# projekt_g_wny_1.net
KiCad netlist of a schematic drawn in EAGLE
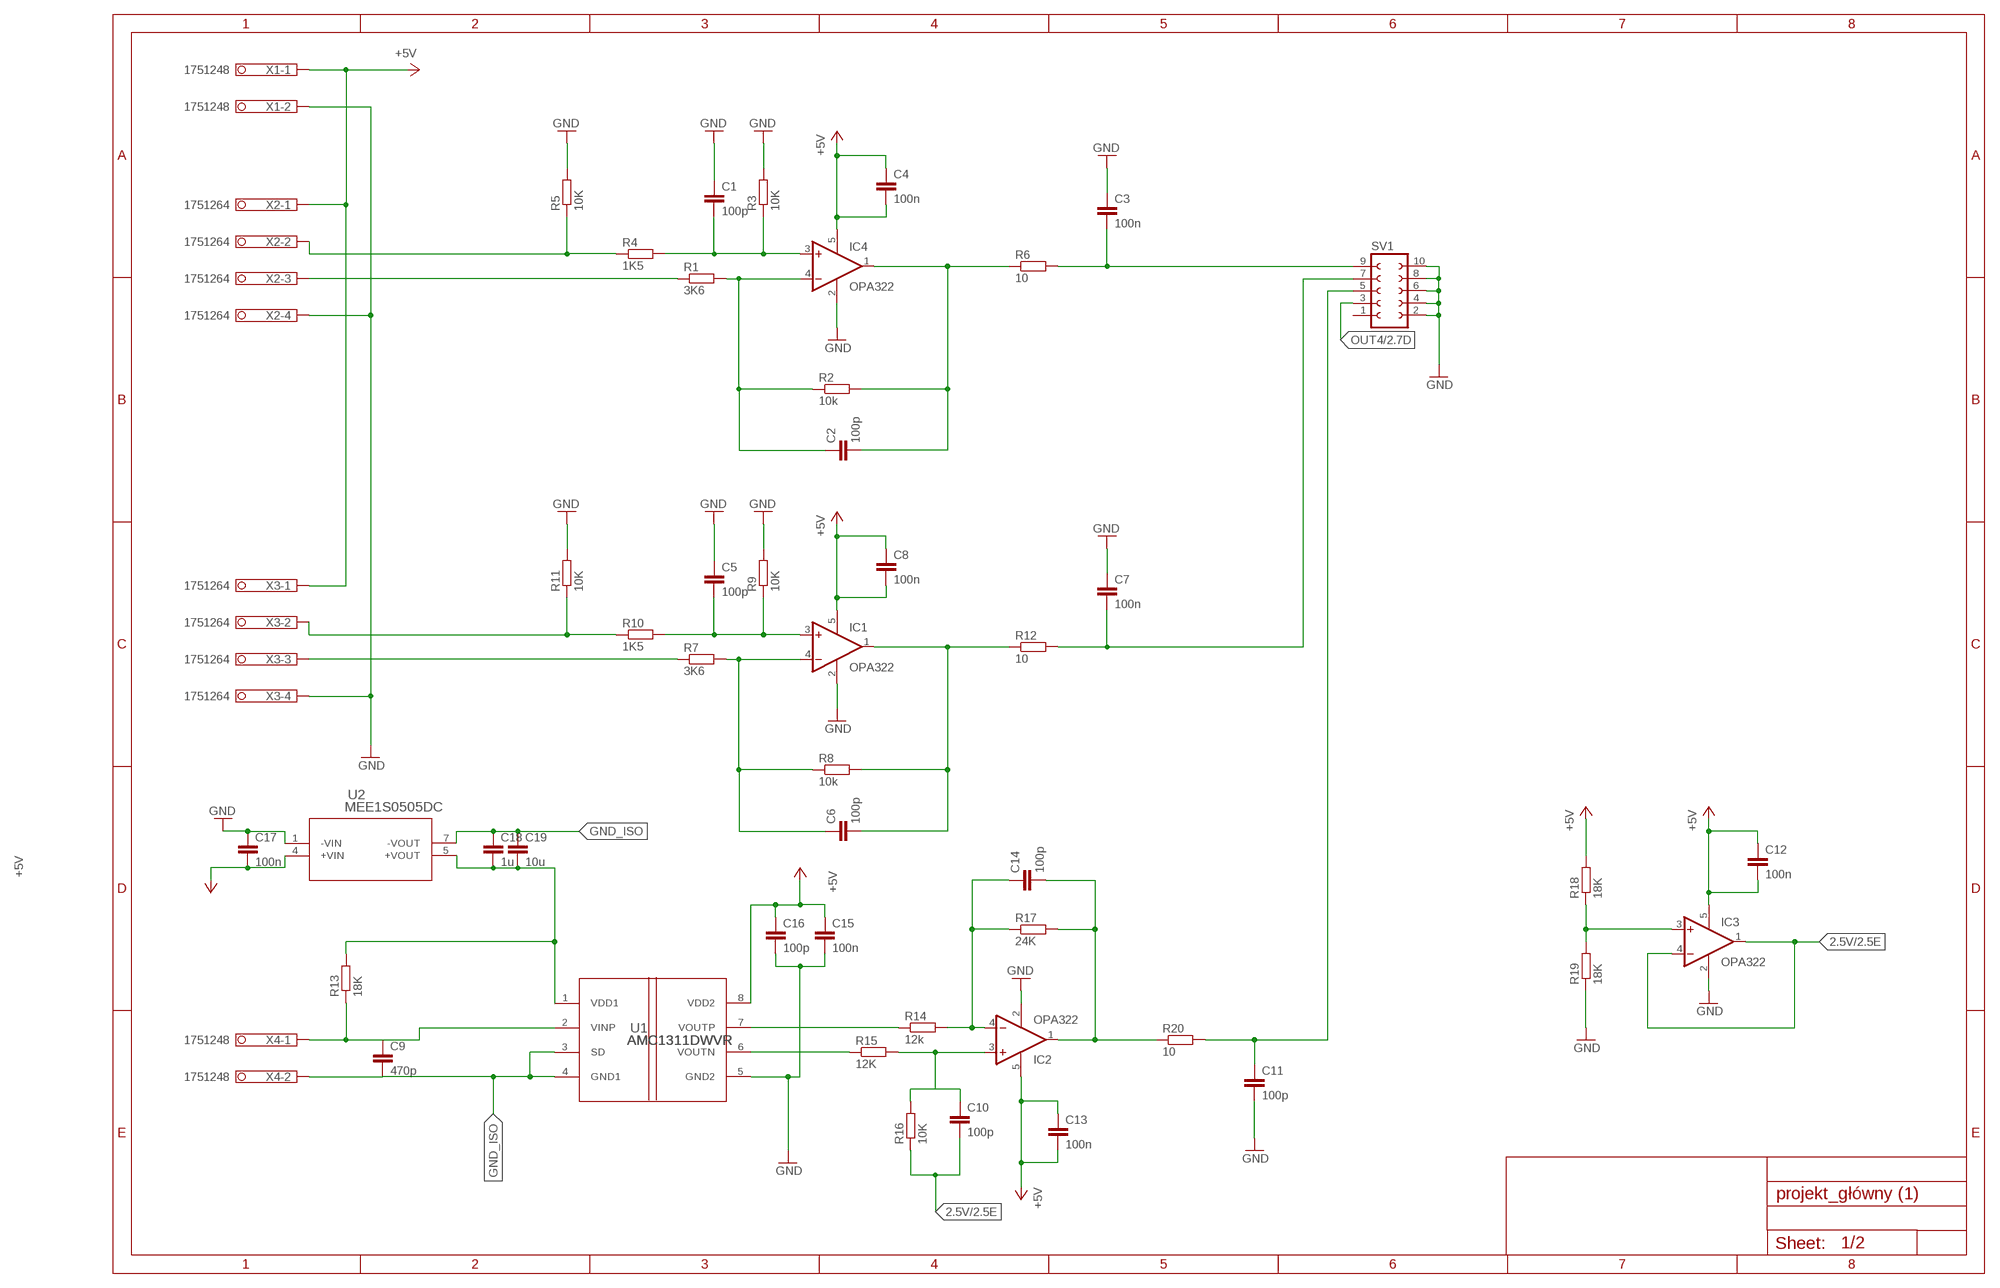
[diagram p0: schematic, sheet 1]
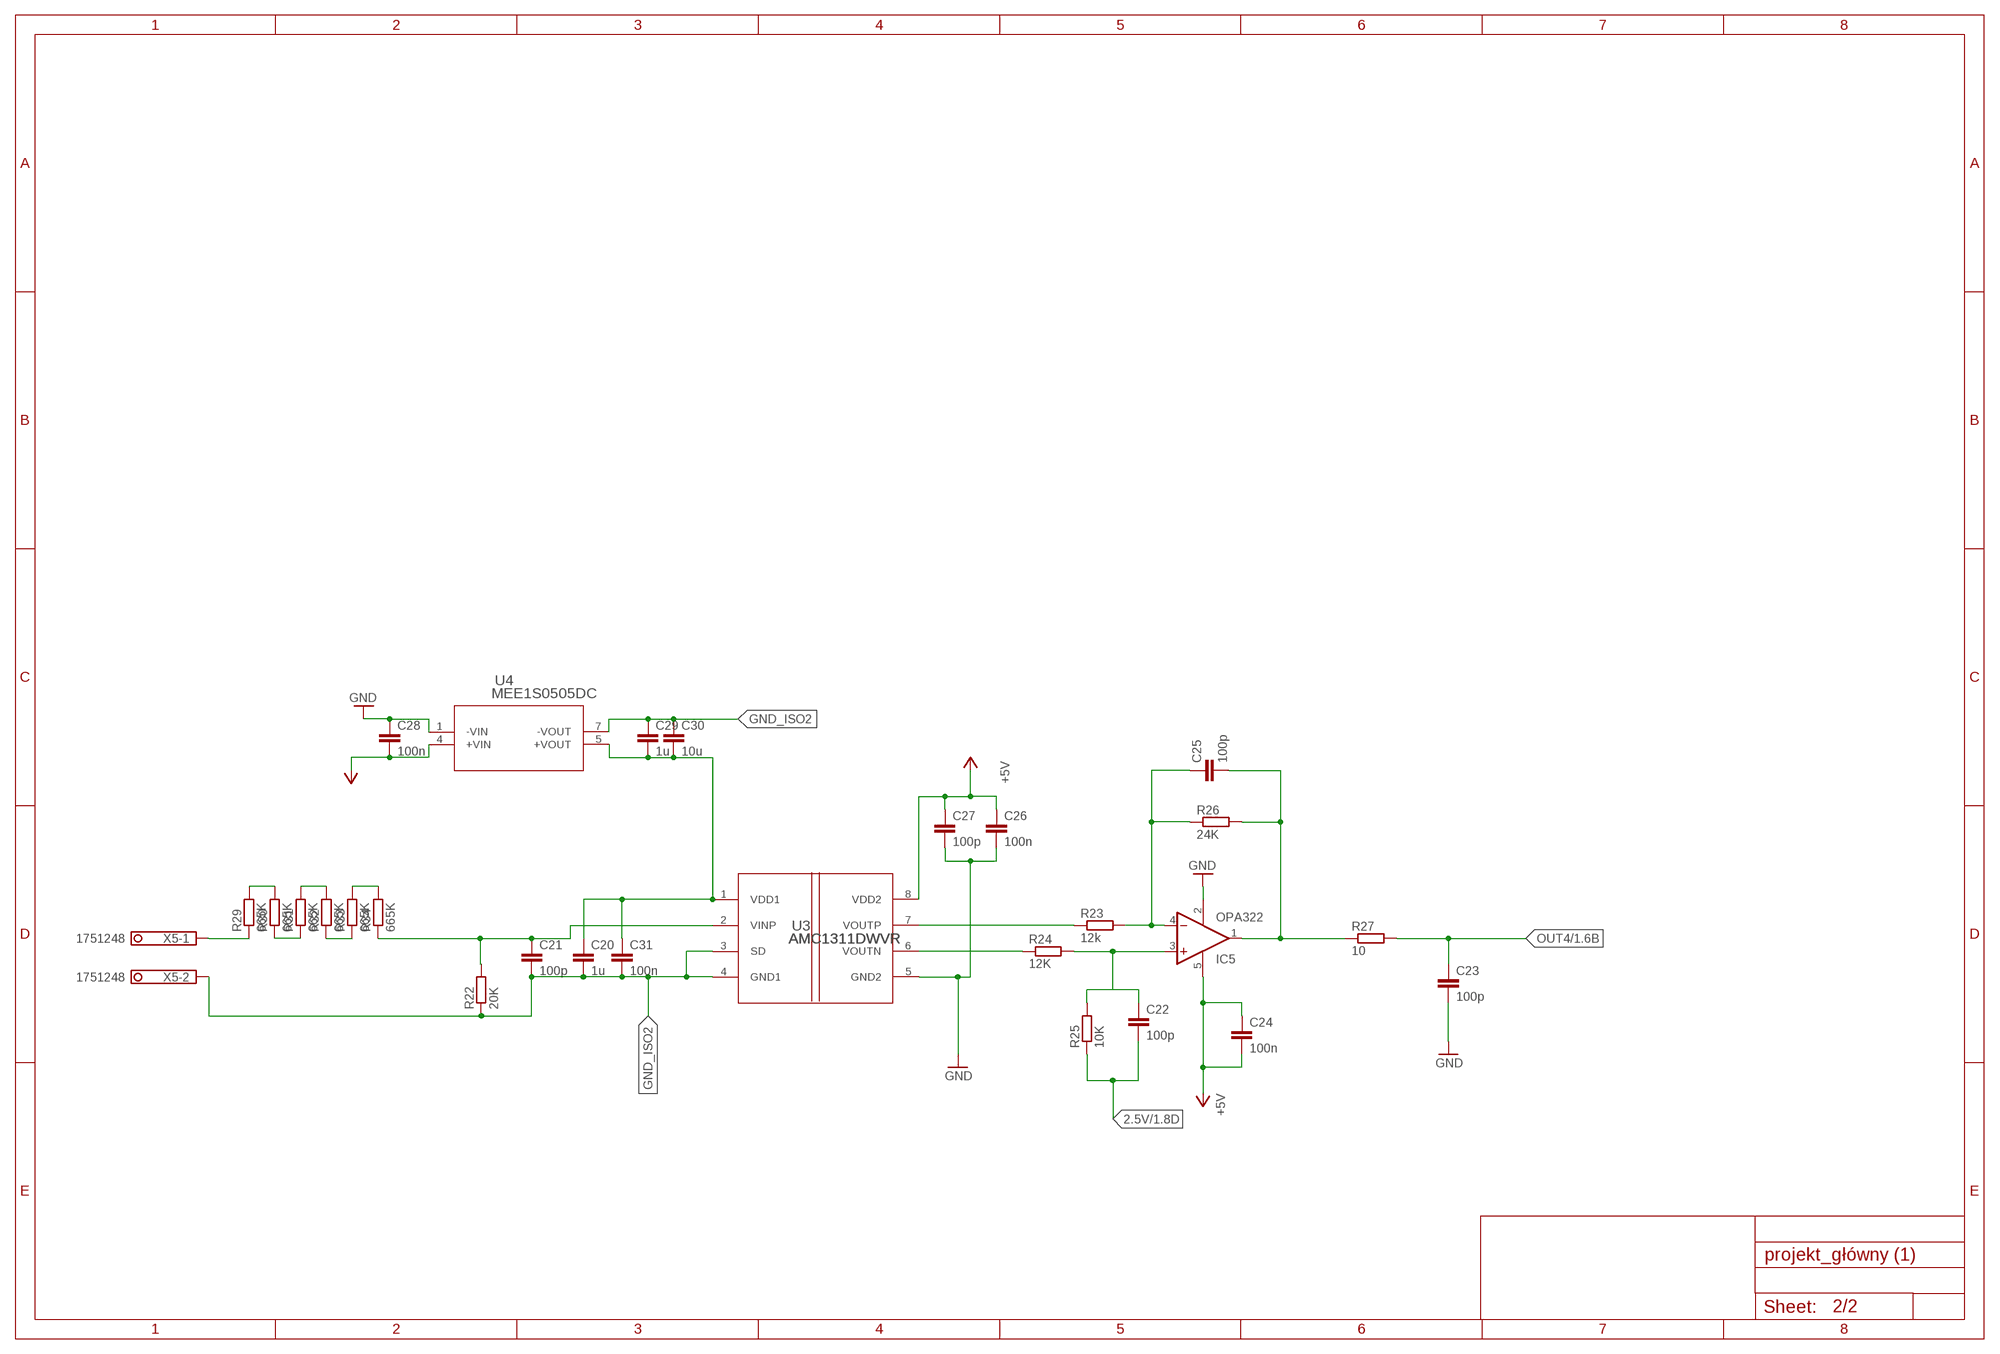
[diagram p1: schematic, sheet 2]

(export (version "E")
  (design (tool "Eeschema 10.0.6"))
  (components
    (comp (ref "C20")
      (value "1u")
      (footprint "eagle-import:C0603")
      (libsource (lib "eagle-import") (part "C-EUC0603"))
    )
    (comp (ref "C21")
      (value "100p")
      (footprint "eagle-import:C0603")
      (libsource (lib "eagle-import") (part "C-EUC0603"))
    )
    (comp (ref "C22")
      (value "100p")
      (footprint "eagle-import:C0603")
      (libsource (lib "eagle-import") (part "C-EUC0603"))
    )
    (comp (ref "C23")
      (value "100p")
      (footprint "eagle-import:C0603")
      (libsource (lib "eagle-import") (part "C-EUC0603"))
    )
    (comp (ref "C24")
      (value "100n")
      (footprint "eagle-import:C0603")
      (libsource (lib "eagle-import") (part "C-EUC0603"))
    )
    (comp (ref "C25")
      (value "100p")
      (footprint "eagle-import:C0603")
      (libsource (lib "eagle-import") (part "C-EUC0603"))
    )
    (comp (ref "C26")
      (value "100n")
      (footprint "eagle-import:C0603")
      (libsource (lib "eagle-import") (part "C-EUC0603"))
    )
    (comp (ref "C27")
      (value "100p")
      (footprint "eagle-import:C0603")
      (libsource (lib "eagle-import") (part "C-EUC0603"))
    )
    (comp (ref "C28")
      (value "100n")
      (footprint "eagle-import:C0603")
      (libsource (lib "eagle-import") (part "C-EUC0603"))
    )
    (comp (ref "C29")
      (value "1u")
      (footprint "eagle-import:C0603")
      (libsource (lib "eagle-import") (part "C-EUC0603"))
    )
    (comp (ref "C30")
      (value "10u")
      (footprint "eagle-import:C0603")
      (libsource (lib "eagle-import") (part "C-EUC0603"))
    )
    (comp (ref "C31")
      (value "100n")
      (footprint "eagle-import:C0603")
      (libsource (lib "eagle-import") (part "C-EUC0603"))
    )
    (comp (ref "IC5")
      (value "OPA322")
      (footprint "eagle-import:SOT23-5")
      (libsource (lib "eagle-import") (part "OPA333DBV"))
    )
    (comp (ref "R22")
      (value "20K")
      (footprint "eagle-import:R0805")
      (libsource (lib "eagle-import") (part "R-EU_R0805"))
    )
    (comp (ref "R23")
      (value "12k")
      (footprint "eagle-import:R0805")
      (libsource (lib "eagle-import") (part "R-EU_R0805"))
    )
    (comp (ref "R24")
      (value "12K")
      (footprint "eagle-import:R0805")
      (libsource (lib "eagle-import") (part "R-EU_R0805"))
    )
    (comp (ref "R25")
      (value "10K")
      (footprint "eagle-import:R0805")
      (libsource (lib "eagle-import") (part "R-EU_R0805"))
    )
    (comp (ref "R26")
      (value "24K")
      (footprint "eagle-import:R0805")
      (libsource (lib "eagle-import") (part "R-EU_R0805"))
    )
    (comp (ref "R27")
      (value "10")
      (footprint "eagle-import:R0805")
      (libsource (lib "eagle-import") (part "R-EU_R0805"))
    )
    (comp (ref "R29")
      (value "665K")
      (footprint "eagle-import:R0805")
      (libsource (lib "eagle-import") (part "R-EU_R0805"))
    )
    (comp (ref "R30")
      (value "665K")
      (footprint "eagle-import:R0805")
      (libsource (lib "eagle-import") (part "R-EU_R0805"))
    )
    (comp (ref "R31")
      (value "665K")
      (footprint "eagle-import:R0805")
      (libsource (lib "eagle-import") (part "R-EU_R0805"))
    )
    (comp (ref "R32")
      (value "665K")
      (footprint "eagle-import:R0805")
      (libsource (lib "eagle-import") (part "R-EU_R0805"))
    )
    (comp (ref "R33")
      (value "665K")
      (footprint "eagle-import:R0805")
      (libsource (lib "eagle-import") (part "R-EU_R0805"))
    )
    (comp (ref "R34")
      (value "665K")
      (footprint "eagle-import:R0805")
      (libsource (lib "eagle-import") (part "R-EU_R0805"))
    )
    (comp (ref "U3")
      (value "AMC1311DWVR")
      (footprint "eagle-import:DWV0008A")
      (fields (field (name "COPYRIGHT") "Copyright (C) 2023 Ultra Librarian. All rights reserved."))
      (libsource (lib "eagle-import") (part "AMC1311DWVR"))
    )
    (comp (ref "U4")
      (value "MEE1S0505DC")
      (footprint "eagle-import:MEE1S0305DC_MUR")
      (fields
        (field (name "MANUFACTURER_PART_NUMBER") "MEE1S0305DC")
        (field (name "COPYRIGHT") "Copyright (C) 2023 Ultra Librarian. All rights reserved.")
      )
      (libsource (lib "eagle-import") (part "MEE1S0305DC"))
    )
    (comp (ref "X5")
      (value "1751248")
      (footprint "eagle-import:1751248")
      (libsource (lib "eagle-import") (part "1751248"))
    )
    (comp (ref "C1")
      (value "100p")
      (footprint "eagle-import:C0603")
      (libsource (lib "eagle-import") (part "C-EUC0603"))
    )
    (comp (ref "C2")
      (value "100p")
      (footprint "eagle-import:C0603")
      (libsource (lib "eagle-import") (part "C-EUC0603"))
    )
    (comp (ref "C3")
      (value "100n")
      (footprint "eagle-import:C0603")
      (libsource (lib "eagle-import") (part "C-EUC0603"))
    )
    (comp (ref "C4")
      (value "100n")
      (footprint "eagle-import:C0603")
      (libsource (lib "eagle-import") (part "C-EUC0603"))
    )
    (comp (ref "C5")
      (value "100p")
      (footprint "eagle-import:C0603")
      (libsource (lib "eagle-import") (part "C-EUC0603"))
    )
    (comp (ref "C6")
      (value "100p")
      (footprint "eagle-import:C0603")
      (libsource (lib "eagle-import") (part "C-EUC0603"))
    )
    (comp (ref "C7")
      (value "100n")
      (footprint "eagle-import:C0603")
      (libsource (lib "eagle-import") (part "C-EUC0603"))
    )
    (comp (ref "C8")
      (value "100n")
      (footprint "eagle-import:C0603")
      (libsource (lib "eagle-import") (part "C-EUC0603"))
    )
    (comp (ref "C9")
      (value "470p")
      (footprint "eagle-import:C0603")
      (libsource (lib "eagle-import") (part "C-EUC0603"))
    )
    (comp (ref "C10")
      (value "100p")
      (footprint "eagle-import:C0603")
      (libsource (lib "eagle-import") (part "C-EUC0603"))
    )
    (comp (ref "C11")
      (value "100p")
      (footprint "eagle-import:C0603")
      (libsource (lib "eagle-import") (part "C-EUC0603"))
    )
    (comp (ref "C12")
      (value "100n")
      (footprint "eagle-import:C0603")
      (libsource (lib "eagle-import") (part "C-EUC0603"))
    )
    (comp (ref "C13")
      (value "100n")
      (footprint "eagle-import:C0603")
      (libsource (lib "eagle-import") (part "C-EUC0603"))
    )
    (comp (ref "C14")
      (value "100p")
      (footprint "eagle-import:C0603")
      (libsource (lib "eagle-import") (part "C-EUC0603"))
    )
    (comp (ref "C15")
      (value "100n")
      (footprint "eagle-import:C0603")
      (libsource (lib "eagle-import") (part "C-EUC0603"))
    )
    (comp (ref "C16")
      (value "100p")
      (footprint "eagle-import:C0603")
      (libsource (lib "eagle-import") (part "C-EUC0603"))
    )
    (comp (ref "C17")
      (value "100n")
      (footprint "eagle-import:C0603")
      (libsource (lib "eagle-import") (part "C-EUC0603"))
    )
    (comp (ref "C18")
      (value "1u")
      (footprint "eagle-import:C0603")
      (libsource (lib "eagle-import") (part "C-EUC0603"))
    )
    (comp (ref "C19")
      (value "10u")
      (footprint "eagle-import:C0603")
      (libsource (lib "eagle-import") (part "C-EUC0603"))
    )
    (comp (ref "IC1")
      (value "OPA322")
      (footprint "eagle-import:SOT23-5")
      (libsource (lib "eagle-import") (part "OPA333DBV"))
    )
    (comp (ref "IC2")
      (value "OPA322")
      (footprint "eagle-import:SOT23-5")
      (libsource (lib "eagle-import") (part "OPA333DBV"))
    )
    (comp (ref "IC3")
      (value "OPA322")
      (footprint "eagle-import:SOT23-5")
      (libsource (lib "eagle-import") (part "OPA333DBV"))
    )
    (comp (ref "IC4")
      (value "OPA322")
      (footprint "eagle-import:SOT23-5")
      (libsource (lib "eagle-import") (part "OPA333DBV"))
    )
    (comp (ref "R1")
      (value "3K6")
      (footprint "eagle-import:R0805")
      (libsource (lib "eagle-import") (part "R-EU_R0805"))
    )
    (comp (ref "R2")
      (value "10k")
      (footprint "eagle-import:R0805")
      (libsource (lib "eagle-import") (part "R-EU_R0805"))
    )
    (comp (ref "R3")
      (value "10K")
      (footprint "eagle-import:R0805")
      (libsource (lib "eagle-import") (part "R-EU_R0805"))
    )
    (comp (ref "R4")
      (value "1K5")
      (footprint "eagle-import:R0805")
      (libsource (lib "eagle-import") (part "R-EU_R0805"))
    )
    (comp (ref "R5")
      (value "10K")
      (footprint "eagle-import:R0805")
      (libsource (lib "eagle-import") (part "R-EU_R0805"))
    )
    (comp (ref "R6")
      (value "10")
      (footprint "eagle-import:R0805")
      (libsource (lib "eagle-import") (part "R-EU_R0805"))
    )
    (comp (ref "R7")
      (value "3K6")
      (footprint "eagle-import:R0805")
      (libsource (lib "eagle-import") (part "R-EU_R0805"))
    )
    (comp (ref "R8")
      (value "10k")
      (footprint "eagle-import:R0805")
      (libsource (lib "eagle-import") (part "R-EU_R0805"))
    )
    (comp (ref "R9")
      (value "10K")
      (footprint "eagle-import:R0805")
      (libsource (lib "eagle-import") (part "R-EU_R0805"))
    )
    (comp (ref "R10")
      (value "1K5")
      (footprint "eagle-import:R0805")
      (libsource (lib "eagle-import") (part "R-EU_R0805"))
    )
    (comp (ref "R11")
      (value "10K")
      (footprint "eagle-import:R0805")
      (libsource (lib "eagle-import") (part "R-EU_R0805"))
    )
    (comp (ref "R12")
      (value "10")
      (footprint "eagle-import:R0805")
      (libsource (lib "eagle-import") (part "R-EU_R0805"))
    )
    (comp (ref "R13")
      (value "18K")
      (footprint "eagle-import:R0805")
      (libsource (lib "eagle-import") (part "R-EU_R0805"))
    )
    (comp (ref "R14")
      (value "12k")
      (footprint "eagle-import:R0805")
      (libsource (lib "eagle-import") (part "R-EU_R0805"))
    )
    (comp (ref "R15")
      (value "12K")
      (footprint "eagle-import:R0805")
      (libsource (lib "eagle-import") (part "R-EU_R0805"))
    )
    (comp (ref "R16")
      (value "10K")
      (footprint "eagle-import:R0805")
      (libsource (lib "eagle-import") (part "R-EU_R0805"))
    )
    (comp (ref "R17")
      (value "24K")
      (footprint "eagle-import:R0805")
      (libsource (lib "eagle-import") (part "R-EU_R0805"))
    )
    (comp (ref "R18")
      (value "18K")
      (footprint "eagle-import:R0805")
      (libsource (lib "eagle-import") (part "R-EU_R0805"))
    )
    (comp (ref "R19")
      (value "18K")
      (footprint "eagle-import:R0805")
      (libsource (lib "eagle-import") (part "R-EU_R0805"))
    )
    (comp (ref "R20")
      (value "10")
      (footprint "eagle-import:R0805")
      (libsource (lib "eagle-import") (part "R-EU_R0805"))
    )
    (comp (ref "SV1")
      (value "FE05-2")
      (footprint "eagle-import:FE05-2")
      (libsource (lib "eagle-import") (part "FE05-2"))
    )
    (comp (ref "U1")
      (value "AMC1311DWVR")
      (footprint "eagle-import:DWV0008A")
      (fields (field (name "COPYRIGHT") "Copyright (C) 2023 Ultra Librarian. All rights reserved."))
      (libsource (lib "eagle-import") (part "AMC1311DWVR"))
    )
    (comp (ref "U2")
      (value "MEE1S0505DC")
      (footprint "eagle-import:MEE1S0305DC_MUR")
      (fields
        (field (name "MANUFACTURER_PART_NUMBER") "MEE1S0305DC")
        (field (name "COPYRIGHT") "Copyright (C) 2023 Ultra Librarian. All rights reserved.")
      )
      (libsource (lib "eagle-import") (part "MEE1S0305DC"))
    )
    (comp (ref "X1")
      (value "1751248")
      (footprint "eagle-import:1751248")
      (libsource (lib "eagle-import") (part "1751248"))
    )
    (comp (ref "X2")
      (value "1751264")
      (footprint "eagle-import:1751264")
      (libsource (lib "eagle-import") (part "1751264"))
    )
    (comp (ref "X3")
      (value "1751264")
      (footprint "eagle-import:1751264")
      (libsource (lib "eagle-import") (part "1751264"))
    )
    (comp (ref "X4")
      (value "1751248")
      (footprint "eagle-import:1751248")
      (libsource (lib "eagle-import") (part "1751248"))
    )
  )
  (nets
    (net (code "1") (name "+5V") (class "Default")
      (node (ref "C12") (pin "1") (pinfunction "1_1") (pintype "passive"))
      (node (ref "C12") (pin "2") (pinfunction "2_2") (pintype "passive"))
      (node (ref "C13") (pin "1") (pinfunction "1_1") (pintype "passive"))
      (node (ref "C13") (pin "2") (pinfunction "2_2") (pintype "passive"))
      (node (ref "C15") (pin "1") (pinfunction "1_1") (pintype "passive"))
      (node (ref "C16") (pin "1") (pinfunction "1_1") (pintype "passive"))
      (node (ref "C17") (pin "2") (pinfunction "2_2") (pintype "passive"))
      (node (ref "C24") (pin "1") (pinfunction "1_1") (pintype "passive"))
      (node (ref "C24") (pin "2") (pinfunction "2_2") (pintype "passive"))
      (node (ref "C26") (pin "1") (pinfunction "1_1") (pintype "passive"))
      (node (ref "C27") (pin "1") (pinfunction "1_1") (pintype "passive"))
      (node (ref "C28") (pin "2") (pinfunction "2_2") (pintype "passive"))
      (node (ref "C4") (pin "1") (pinfunction "1_1") (pintype "passive"))
      (node (ref "C4") (pin "2") (pinfunction "2_2") (pintype "passive"))
      (node (ref "C8") (pin "1") (pinfunction "1_1") (pintype "passive"))
      (node (ref "C8") (pin "2") (pinfunction "2_2") (pintype "passive"))
      (node (ref "IC1") (pin "5") (pinfunction "V+_5") (pintype "power_in"))
      (node (ref "IC2") (pin "5") (pinfunction "V+_5") (pintype "power_in"))
      (node (ref "IC3") (pin "5") (pinfunction "V+_5") (pintype "power_in"))
      (node (ref "IC4") (pin "5") (pinfunction "V+_5") (pintype "power_in"))
      (node (ref "IC5") (pin "5") (pinfunction "V+_5") (pintype "power_in"))
      (node (ref "R18") (pin "2") (pinfunction "2_2") (pintype "passive"))
      (node (ref "U1") (pin "8") (pinfunction "VDD2_8") (pintype "power_in"))
      (node (ref "U2") (pin "4") (pinfunction "+VIN_4") (pintype "power_in"))
      (node (ref "U3") (pin "8") (pinfunction "VDD2_8") (pintype "power_in"))
      (node (ref "U4") (pin "4") (pinfunction "+VIN_4") (pintype "power_in"))
      (node (ref "X1") (pin "1") (pinfunction "K_1") (pintype "passive"))
      (node (ref "X2") (pin "1") (pinfunction "K_1") (pintype "passive"))
      (node (ref "X3") (pin "1") (pinfunction "K_1") (pintype "passive"))
    )
    (net (code "2") (name "2.5V") (class "Default")
      (node (ref "C10") (pin "2") (pinfunction "2_2") (pintype "passive"))
      (node (ref "C22") (pin "2") (pinfunction "2_2") (pintype "passive"))
      (node (ref "IC3") (pin "1") (pinfunction "OUT_1") (pintype "output"))
      (node (ref "IC3") (pin "4") (pinfunction "-IN_4") (pintype "input"))
      (node (ref "R16") (pin "1") (pinfunction "1_1") (pintype "passive"))
      (node (ref "R25") (pin "1") (pinfunction "1_1") (pintype "passive"))
    )
    (net (code "3") (name "GND") (class "Default")
      (node (ref "C1") (pin "1") (pinfunction "1_1") (pintype "passive"))
      (node (ref "C11") (pin "2") (pinfunction "2_2") (pintype "passive"))
      (node (ref "C15") (pin "2") (pinfunction "2_2") (pintype "passive"))
      (node (ref "C16") (pin "2") (pinfunction "2_2") (pintype "passive"))
      (node (ref "C17") (pin "1") (pinfunction "1_1") (pintype "passive"))
      (node (ref "C23") (pin "2") (pinfunction "2_2") (pintype "passive"))
      (node (ref "C26") (pin "2") (pinfunction "2_2") (pintype "passive"))
      (node (ref "C27") (pin "2") (pinfunction "2_2") (pintype "passive"))
      (node (ref "C28") (pin "1") (pinfunction "1_1") (pintype "passive"))
      (node (ref "C3") (pin "1") (pinfunction "1_1") (pintype "passive"))
      (node (ref "C5") (pin "1") (pinfunction "1_1") (pintype "passive"))
      (node (ref "C7") (pin "1") (pinfunction "1_1") (pintype "passive"))
      (node (ref "IC1") (pin "2") (pinfunction "V-_2") (pintype "power_in"))
      (node (ref "IC2") (pin "2") (pinfunction "V-_2") (pintype "power_in"))
      (node (ref "IC3") (pin "2") (pinfunction "V-_2") (pintype "power_in"))
      (node (ref "IC4") (pin "2") (pinfunction "V-_2") (pintype "power_in"))
      (node (ref "IC5") (pin "2") (pinfunction "V-_2") (pintype "power_in"))
      (node (ref "R11") (pin "2") (pinfunction "2_2") (pintype "passive"))
      (node (ref "R19") (pin "1") (pinfunction "1_1") (pintype "passive"))
      (node (ref "R3") (pin "2") (pinfunction "2_2") (pintype "passive"))
      (node (ref "R5") (pin "2") (pinfunction "2_2") (pintype "passive"))
      (node (ref "R9") (pin "2") (pinfunction "2_2") (pintype "passive"))
      (node (ref "SV1") (pin "10") (pinfunction "10_10") (pintype "passive"))
      (node (ref "SV1") (pin "2") (pinfunction "2_2") (pintype "passive"))
      (node (ref "SV1") (pin "4") (pinfunction "4_4") (pintype "passive"))
      (node (ref "SV1") (pin "6") (pinfunction "6_6") (pintype "passive"))
      (node (ref "SV1") (pin "8") (pinfunction "8_8") (pintype "passive"))
      (node (ref "U1") (pin "5") (pinfunction "GND2_5") (pintype "power_in"))
      (node (ref "U2") (pin "1") (pinfunction "-VIN_1") (pintype "power_in"))
      (node (ref "U3") (pin "5") (pinfunction "GND2_5") (pintype "power_in"))
      (node (ref "U4") (pin "1") (pinfunction "-VIN_1") (pintype "power_in"))
      (node (ref "X1") (pin "2") (pinfunction "K_2") (pintype "passive"))
      (node (ref "X2") (pin "4") (pinfunction "K_4") (pintype "passive"))
      (node (ref "X3") (pin "4") (pinfunction "K_4") (pintype "passive"))
    )
    (net (code "4") (name "GND_ISO") (class "Default")
      (node (ref "C18") (pin "1") (pinfunction "1_1") (pintype "passive"))
      (node (ref "C19") (pin "1") (pinfunction "1_1") (pintype "passive"))
      (node (ref "C9") (pin "2") (pinfunction "2_2") (pintype "passive"))
      (node (ref "U1") (pin "3") (pinfunction "SD_3") (pintype "input"))
      (node (ref "U1") (pin "4") (pinfunction "GND1_4") (pintype "power_in"))
      (node (ref "U2") (pin "7") (pinfunction "-VOUT_7") (pintype "output"))
      (node (ref "X4") (pin "2") (pinfunction "K_2") (pintype "passive"))
    )
    (net (code "5") (name "GND_ISO2") (class "Default")
      (node (ref "C20") (pin "2") (pinfunction "2_2") (pintype "passive"))
      (node (ref "C21") (pin "2") (pinfunction "2_2") (pintype "passive"))
      (node (ref "C29") (pin "1") (pinfunction "1_1") (pintype "passive"))
      (node (ref "C30") (pin "1") (pinfunction "1_1") (pintype "passive"))
      (node (ref "C31") (pin "2") (pinfunction "2_2") (pintype "passive"))
      (node (ref "R22") (pin "1") (pinfunction "1_1") (pintype "passive"))
      (node (ref "U3") (pin "3") (pinfunction "SD_3") (pintype "input"))
      (node (ref "U3") (pin "4") (pinfunction "GND1_4") (pintype "power_in"))
      (node (ref "U4") (pin "7") (pinfunction "-VOUT_7") (pintype "output"))
      (node (ref "X5") (pin "2") (pinfunction "K_2") (pintype "passive"))
    )
    (net (code "6") (name "Net-(C3-Pad2)") (class "Default")
      (node (ref "C3") (pin "2") (pinfunction "2_2") (pintype "passive"))
      (node (ref "R6") (pin "2") (pinfunction "2_2") (pintype "passive"))
      (node (ref "SV1") (pin "9") (pinfunction "9_9") (pintype "passive"))
    )
    (net (code "7") (name "Net-(C7-Pad2)") (class "Default")
      (node (ref "C7") (pin "2") (pinfunction "2_2") (pintype "passive"))
      (node (ref "R12") (pin "2") (pinfunction "2_2") (pintype "passive"))
      (node (ref "SV1") (pin "7") (pinfunction "7_7") (pintype "passive"))
    )
    (net (code "8") (name "Net-(C11-Pad1)") (class "Default")
      (node (ref "C11") (pin "1") (pinfunction "1_1") (pintype "passive"))
      (node (ref "R20") (pin "2") (pinfunction "2_2") (pintype "passive"))
      (node (ref "SV1") (pin "5") (pinfunction "5_5") (pintype "passive"))
    )
    (net (code "9") (name "Net-(IC1-+IN)") (class "Default")
      (node (ref "C5") (pin "2") (pinfunction "2_2") (pintype "passive"))
      (node (ref "IC1") (pin "3") (pinfunction "+IN_3") (pintype "input"))
      (node (ref "R10") (pin "2") (pinfunction "2_2") (pintype "passive"))
      (node (ref "R9") (pin "1") (pinfunction "1_1") (pintype "passive"))
    )
    (net (code "10") (name "Net-(IC1--IN)") (class "Default")
      (node (ref "C6") (pin "1") (pinfunction "1_1") (pintype "passive"))
      (node (ref "IC1") (pin "4") (pinfunction "-IN_4") (pintype "input"))
      (node (ref "R7") (pin "2") (pinfunction "2_2") (pintype "passive"))
      (node (ref "R8") (pin "1") (pinfunction "1_1") (pintype "passive"))
    )
    (net (code "11") (name "Net-(IC1-OUT)") (class "Default")
      (node (ref "C6") (pin "2") (pinfunction "2_2") (pintype "passive"))
      (node (ref "IC1") (pin "1") (pinfunction "OUT_1") (pintype "output"))
      (node (ref "R12") (pin "1") (pinfunction "1_1") (pintype "passive"))
      (node (ref "R8") (pin "2") (pinfunction "2_2") (pintype "passive"))
    )
    (net (code "12") (name "Net-(IC2-+IN)") (class "Default")
      (node (ref "C10") (pin "1") (pinfunction "1_1") (pintype "passive"))
      (node (ref "IC2") (pin "3") (pinfunction "+IN_3") (pintype "input"))
      (node (ref "R15") (pin "2") (pinfunction "2_2") (pintype "passive"))
      (node (ref "R16") (pin "2") (pinfunction "2_2") (pintype "passive"))
    )
    (net (code "13") (name "Net-(IC2--IN)") (class "Default")
      (node (ref "C14") (pin "1") (pinfunction "1_1") (pintype "passive"))
      (node (ref "IC2") (pin "4") (pinfunction "-IN_4") (pintype "input"))
      (node (ref "R14") (pin "2") (pinfunction "2_2") (pintype "passive"))
      (node (ref "R17") (pin "1") (pinfunction "1_1") (pintype "passive"))
    )
    (net (code "14") (name "Net-(IC2-OUT)") (class "Default")
      (node (ref "C14") (pin "2") (pinfunction "2_2") (pintype "passive"))
      (node (ref "IC2") (pin "1") (pinfunction "OUT_1") (pintype "output"))
      (node (ref "R17") (pin "2") (pinfunction "2_2") (pintype "passive"))
      (node (ref "R20") (pin "1") (pinfunction "1_1") (pintype "passive"))
    )
    (net (code "15") (name "Net-(IC3-+IN)") (class "Default")
      (node (ref "IC3") (pin "3") (pinfunction "+IN_3") (pintype "input"))
      (node (ref "R18") (pin "1") (pinfunction "1_1") (pintype "passive"))
      (node (ref "R19") (pin "2") (pinfunction "2_2") (pintype "passive"))
    )
    (net (code "16") (name "Net-(IC4-+IN)") (class "Default")
      (node (ref "C1") (pin "2") (pinfunction "2_2") (pintype "passive"))
      (node (ref "IC4") (pin "3") (pinfunction "+IN_3") (pintype "input"))
      (node (ref "R3") (pin "1") (pinfunction "1_1") (pintype "passive"))
      (node (ref "R4") (pin "2") (pinfunction "2_2") (pintype "passive"))
    )
    (net (code "17") (name "Net-(IC4--IN)") (class "Default")
      (node (ref "C2") (pin "1") (pinfunction "1_1") (pintype "passive"))
      (node (ref "IC4") (pin "4") (pinfunction "-IN_4") (pintype "input"))
      (node (ref "R1") (pin "2") (pinfunction "2_2") (pintype "passive"))
      (node (ref "R2") (pin "1") (pinfunction "1_1") (pintype "passive"))
    )
    (net (code "18") (name "Net-(IC4-OUT)") (class "Default")
      (node (ref "C2") (pin "2") (pinfunction "2_2") (pintype "passive"))
      (node (ref "IC4") (pin "1") (pinfunction "OUT_1") (pintype "output"))
      (node (ref "R2") (pin "2") (pinfunction "2_2") (pintype "passive"))
      (node (ref "R6") (pin "1") (pinfunction "1_1") (pintype "passive"))
    )
    (net (code "19") (name "Net-(IC5-+IN)") (class "Default")
      (node (ref "C22") (pin "1") (pinfunction "1_1") (pintype "passive"))
      (node (ref "IC5") (pin "3") (pinfunction "+IN_3") (pintype "input"))
      (node (ref "R24") (pin "2") (pinfunction "2_2") (pintype "passive"))
      (node (ref "R25") (pin "2") (pinfunction "2_2") (pintype "passive"))
    )
    (net (code "20") (name "Net-(IC5--IN)") (class "Default")
      (node (ref "C25") (pin "1") (pinfunction "1_1") (pintype "passive"))
      (node (ref "IC5") (pin "4") (pinfunction "-IN_4") (pintype "input"))
      (node (ref "R23") (pin "2") (pinfunction "2_2") (pintype "passive"))
      (node (ref "R26") (pin "1") (pinfunction "1_1") (pintype "passive"))
    )
    (net (code "21") (name "Net-(IC5-OUT)") (class "Default")
      (node (ref "C25") (pin "2") (pinfunction "2_2") (pintype "passive"))
      (node (ref "IC5") (pin "1") (pinfunction "OUT_1") (pintype "output"))
      (node (ref "R26") (pin "2") (pinfunction "2_2") (pintype "passive"))
      (node (ref "R27") (pin "1") (pinfunction "1_1") (pintype "passive"))
    )
    (net (code "22") (name "Net-(R29-Pad2)") (class "Default")
      (node (ref "R29") (pin "2") (pinfunction "2_2") (pintype "passive"))
      (node (ref "R30") (pin "2") (pinfunction "2_2") (pintype "passive"))
    )
    (net (code "23") (name "Net-(R30-Pad1)") (class "Default")
      (node (ref "R30") (pin "1") (pinfunction "1_1") (pintype "passive"))
      (node (ref "R31") (pin "1") (pinfunction "1_1") (pintype "passive"))
    )
    (net (code "24") (name "Net-(R31-Pad2)") (class "Default")
      (node (ref "R31") (pin "2") (pinfunction "2_2") (pintype "passive"))
      (node (ref "R32") (pin "2") (pinfunction "2_2") (pintype "passive"))
    )
    (net (code "25") (name "Net-(R32-Pad1)") (class "Default")
      (node (ref "R32") (pin "1") (pinfunction "1_1") (pintype "passive"))
      (node (ref "R33") (pin "1") (pinfunction "1_1") (pintype "passive"))
    )
    (net (code "26") (name "Net-(R33-Pad2)") (class "Default")
      (node (ref "R33") (pin "2") (pinfunction "2_2") (pintype "passive"))
      (node (ref "R34") (pin "2") (pinfunction "2_2") (pintype "passive"))
    )
    (net (code "27") (name "Net-(U1-VDD1)") (class "Default")
      (node (ref "C18") (pin "2") (pinfunction "2_2") (pintype "passive"))
      (node (ref "C19") (pin "2") (pinfunction "2_2") (pintype "passive"))
      (node (ref "R13") (pin "2") (pinfunction "2_2") (pintype "passive"))
      (node (ref "U1") (pin "1") (pinfunction "VDD1_1") (pintype "power_in"))
      (node (ref "U2") (pin "5") (pinfunction "+VOUT_5") (pintype "output"))
    )
    (net (code "28") (name "Net-(U1-VINP)") (class "Default")
      (node (ref "C9") (pin "1") (pinfunction "1_1") (pintype "passive"))
      (node (ref "R13") (pin "1") (pinfunction "1_1") (pintype "passive"))
      (node (ref "U1") (pin "2") (pinfunction "VINP_2") (pintype "input"))
      (node (ref "X4") (pin "1") (pinfunction "K_1") (pintype "passive"))
    )
    (net (code "29") (name "Net-(U1-VOUTN)") (class "Default")
      (node (ref "R15") (pin "1") (pinfunction "1_1") (pintype "passive"))
      (node (ref "U1") (pin "6") (pinfunction "VOUTN_6") (pintype "output"))
    )
    (net (code "30") (name "Net-(U1-VOUTP)") (class "Default")
      (node (ref "R14") (pin "1") (pinfunction "1_1") (pintype "passive"))
      (node (ref "U1") (pin "7") (pinfunction "VOUTP_7") (pintype "output"))
    )
    (net (code "31") (name "Net-(U3-VDD1)") (class "Default")
      (node (ref "C20") (pin "1") (pinfunction "1_1") (pintype "passive"))
      (node (ref "C29") (pin "2") (pinfunction "2_2") (pintype "passive"))
      (node (ref "C30") (pin "2") (pinfunction "2_2") (pintype "passive"))
      (node (ref "C31") (pin "1") (pinfunction "1_1") (pintype "passive"))
      (node (ref "U3") (pin "1") (pinfunction "VDD1_1") (pintype "power_in"))
      (node (ref "U4") (pin "5") (pinfunction "+VOUT_5") (pintype "output"))
    )
    (net (code "32") (name "Net-(U3-VINP)") (class "Default")
      (node (ref "C21") (pin "1") (pinfunction "1_1") (pintype "passive"))
      (node (ref "R22") (pin "2") (pinfunction "2_2") (pintype "passive"))
      (node (ref "R34") (pin "1") (pinfunction "1_1") (pintype "passive"))
      (node (ref "U3") (pin "2") (pinfunction "VINP_2") (pintype "input"))
    )
    (net (code "33") (name "Net-(U3-VOUTN)") (class "Default")
      (node (ref "R24") (pin "1") (pinfunction "1_1") (pintype "passive"))
      (node (ref "U3") (pin "6") (pinfunction "VOUTN_6") (pintype "output"))
    )
    (net (code "34") (name "Net-(U3-VOUTP)") (class "Default")
      (node (ref "R23") (pin "1") (pinfunction "1_1") (pintype "passive"))
      (node (ref "U3") (pin "7") (pinfunction "VOUTP_7") (pintype "output"))
    )
    (net (code "35") (name "Net-(X2B-K)") (class "Default")
      (node (ref "R4") (pin "1") (pinfunction "1_1") (pintype "passive"))
      (node (ref "R5") (pin "1") (pinfunction "1_1") (pintype "passive"))
      (node (ref "X2") (pin "2") (pinfunction "K_2") (pintype "passive"))
    )
    (net (code "36") (name "Net-(X2C-K)") (class "Default")
      (node (ref "R1") (pin "1") (pinfunction "1_1") (pintype "passive"))
      (node (ref "X2") (pin "3") (pinfunction "K_3") (pintype "passive"))
    )
    (net (code "37") (name "Net-(X3B-K)") (class "Default")
      (node (ref "R10") (pin "1") (pinfunction "1_1") (pintype "passive"))
      (node (ref "R11") (pin "1") (pinfunction "1_1") (pintype "passive"))
      (node (ref "X3") (pin "2") (pinfunction "K_2") (pintype "passive"))
    )
    (net (code "38") (name "Net-(X3C-K)") (class "Default")
      (node (ref "R7") (pin "1") (pinfunction "1_1") (pintype "passive"))
      (node (ref "X3") (pin "3") (pinfunction "K_3") (pintype "passive"))
    )
    (net (code "39") (name "Net-(X5A-K)") (class "Default")
      (node (ref "R29") (pin "1") (pinfunction "1_1") (pintype "passive"))
      (node (ref "X5") (pin "1") (pinfunction "K_1") (pintype "passive"))
    )
    (net (code "40") (name "OUT4") (class "Default")
      (node (ref "C23") (pin "1") (pinfunction "1_1") (pintype "passive"))
      (node (ref "R27") (pin "2") (pinfunction "2_2") (pintype "passive"))
      (node (ref "SV1") (pin "3") (pinfunction "3_3") (pintype "passive"))
    )
    (net (code "41") (name "unconnected-(SV1-Pad1)") (class "Default")
      (node (ref "SV1") (pin "1") (pinfunction "1_1") (pintype "passive"))
    )
  )
)
